# T32_ref.net
KiCad netlist of a schematic drawn in EAGLE
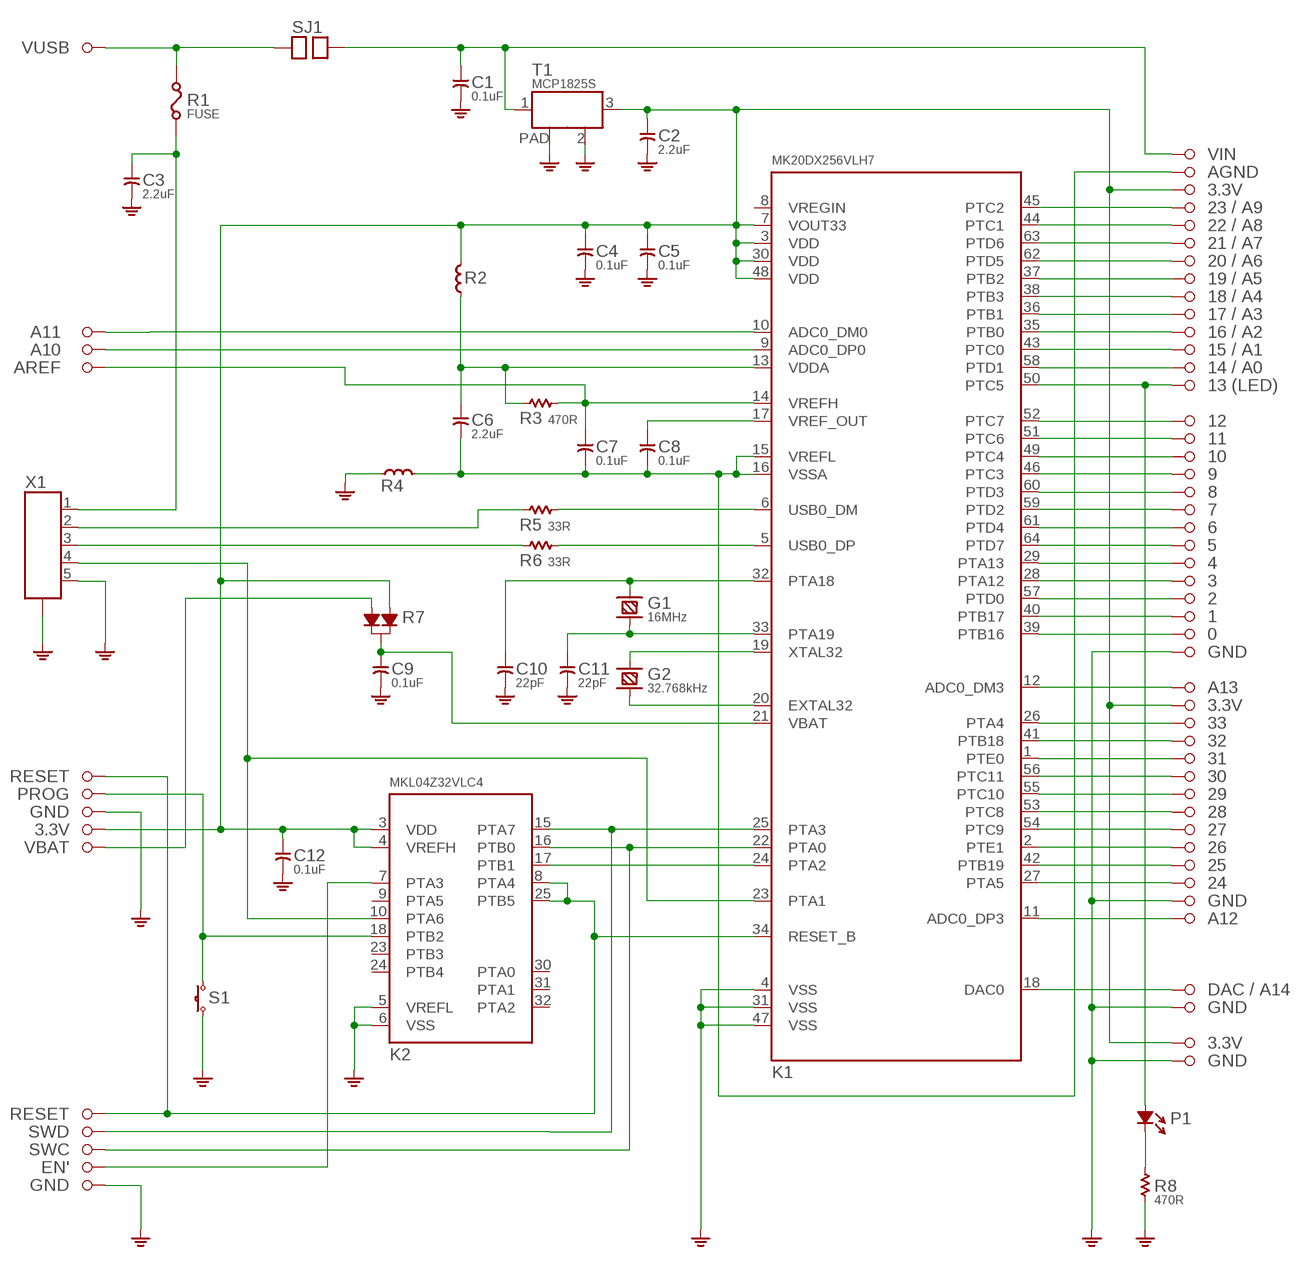
[diagram p0: schematic, sheet 1]

(export (version "E")
  (design (tool "Eeschema 10.0.6"))
  (components
    (comp (ref "C1")
      (value "0.1uF")
      (footprint "eagle-import:C0603")
      (fields (field (name "MF") "Murata Electronics") (field (name "MPN") "GRM155R71A104KA01D"))
      (libsource (lib "eagle-import") (part "CAPACITOR-0.1UF"))
    )
    (comp (ref "C2")
      (value "2.2uF")
      (footprint "eagle-import:C0805")
      (fields (field (name "MF") "Taiyo Yuden") (field (name "MPN") "TMK212B7225KG-TR"))
      (libsource (lib "eagle-import") (part "CAPACITOR-2.2UF"))
    )
    (comp (ref "C3")
      (value "2.2uF")
      (footprint "eagle-import:C0805")
      (fields (field (name "MF") "Taiyo Yuden") (field (name "MPN") "TMK212B7225KG-TR"))
      (libsource (lib "eagle-import") (part "CAPACITOR-2.2UF"))
    )
    (comp (ref "C4")
      (value "0.1uF")
      (footprint "eagle-import:C0603")
      (fields (field (name "MF") "Murata Electronics") (field (name "MPN") "GRM155R71A104KA01D"))
      (libsource (lib "eagle-import") (part "CAPACITOR-0.1UF"))
    )
    (comp (ref "C5")
      (value "0.1uF")
      (footprint "eagle-import:C0603")
      (fields (field (name "MF") "Murata Electronics") (field (name "MPN") "GRM155R71A104KA01D"))
      (libsource (lib "eagle-import") (part "CAPACITOR-0.1UF"))
    )
    (comp (ref "C6")
      (value "2.2uF")
      (footprint "eagle-import:C0805")
      (fields (field (name "MF") "Taiyo Yuden") (field (name "MPN") "TMK212B7225KG-TR"))
      (libsource (lib "eagle-import") (part "CAPACITOR-2.2UF"))
    )
    (comp (ref "C7")
      (value "0.1uF")
      (footprint "eagle-import:C0603")
      (fields (field (name "MF") "Murata Electronics") (field (name "MPN") "GRM155R71A104KA01D"))
      (libsource (lib "eagle-import") (part "CAPACITOR-0.1UF"))
    )
    (comp (ref "C8")
      (value "0.1uF")
      (footprint "eagle-import:C0603")
      (fields (field (name "MF") "Murata Electronics") (field (name "MPN") "GRM155R71A104KA01D"))
      (libsource (lib "eagle-import") (part "CAPACITOR-0.1UF"))
    )
    (comp (ref "C9")
      (value "0.1uF")
      (footprint "eagle-import:C0603")
      (fields (field (name "MF") "Murata Electronics") (field (name "MPN") "GRM155R71A104KA01D"))
      (libsource (lib "eagle-import") (part "CAPACITOR-0.1UF"))
    )
    (comp (ref "C10")
      (value "22pF")
      (footprint "eagle-import:C0603")
      (fields (field (name "MF") "Vishay / Vitramon") (field (name "MPN") "VJ0603A220JXACW1BC"))
      (libsource (lib "eagle-import") (part "CAPACITOR-22PF"))
    )
    (comp (ref "C11")
      (value "22pF")
      (footprint "eagle-import:C0603")
      (fields (field (name "MF") "Vishay / Vitramon") (field (name "MPN") "VJ0603A220JXACW1BC"))
      (libsource (lib "eagle-import") (part "CAPACITOR-22PF"))
    )
    (comp (ref "C12")
      (value "0.1uF")
      (footprint "eagle-import:C0603")
      (fields (field (name "MF") "Murata Electronics") (field (name "MPN") "GRM155R71A104KA01D"))
      (libsource (lib "eagle-import") (part "CAPACITOR-0.1UF"))
    )
    (comp (ref "G1")
      (value "16MHz")
      (footprint "eagle-import:HC49US")
      (fields (field (name "MF") "ABRACON") (field (name "MPN") "ABL-16.000MHz-B1U"))
      (libsource (lib "eagle-import") (part "CRYSTAL-HC49US"))
    )
    (comp (ref "G2")
      (value "32.768kHz")
      (footprint "eagle-import:TC26H")
      (fields (field (name "MF") "Citizen FineDevice") (field (name "MPN") " CFS206-32.768KDZF-UB"))
      (libsource (lib "eagle-import") (part "CRYSTAL-TC26H"))
    )
    (comp (ref "K1")
      (value "MK20DX256VLH7")
      (footprint "eagle-import:LQFP64-05")
      (fields (field (name "MF") "NXP"))
      (libsource (lib "eagle-import") (part "MK20DX256VLH7"))
    )
    (comp (ref "K2")
      (value "MKL04Z32VLC4")
      (footprint "eagle-import:LQFP32-08")
      (fields (field (name "MF") "PJRC") (field (name "MPN") "IC_MKL04Z32_TQFP32"))
      (libsource (lib "eagle-import") (part "MKL04Z32VLC4"))
    )
    (comp (ref "P1")
      (value "LED")
      (footprint "eagle-import:LED-0805")
      (fields (field (name "MF") "ROHM Semiconductor") (field (name "MPN") "SML-211DTT86"))
      (libsource (lib "eagle-import") (part "LED"))
    )
    (comp (ref "R1")
      (value "FUSE")
      (footprint "eagle-import:F0805")
      (fields (field (name "MF") "Bel Fuse") (field (name "MPN") "0ZCK0050FF2E"))
      (libsource (lib "eagle-import") (part "FUSE"))
    )
    (comp (ref "R2")
      (value "FERRITE")
      (footprint "eagle-import:L0603")
      (fields (field (name "MF") "Murata Electronics") (field (name "MPN") " BLM18AG601SN1D"))
      (libsource (lib "eagle-import") (part "FERRITE"))
    )
    (comp (ref "R3")
      (value "470R")
      (footprint "eagle-import:R0603")
      (fields (field (name "MF") "Vishay") (field (name "MPN") "CRCW0603470RFKEA"))
      (libsource (lib "eagle-import") (part "RESISTOR-470R"))
    )
    (comp (ref "R4")
      (value "FERRITE")
      (footprint "eagle-import:L0603")
      (fields (field (name "MF") "Murata Electronics") (field (name "MPN") " BLM18AG601SN1D"))
      (libsource (lib "eagle-import") (part "FERRITE"))
    )
    (comp (ref "R5")
      (value "33R")
      (footprint "eagle-import:R0603")
      (fields (field (name "MF") "Panasonic") (field (name "MPN") "ERJ-PA3F33R0V"))
      (libsource (lib "eagle-import") (part "RESISTOR-33R"))
    )
    (comp (ref "R6")
      (value "33R")
      (footprint "eagle-import:R0603")
      (fields (field (name "MF") "Panasonic") (field (name "MPN") "ERJ-PA3F33R0V"))
      (libsource (lib "eagle-import") (part "RESISTOR-33R"))
    )
    (comp (ref "R7")
      (value "DIODE_DUAL")
      (footprint "eagle-import:SOT-23")
      (fields (field (name "MF") "NXP Semiconductors") (field (name "MPN") "BAT54C,215"))
      (libsource (lib "eagle-import") (part "DIODE_DUAL"))
    )
    (comp (ref "R8")
      (value "470R")
      (footprint "eagle-import:R0603")
      (fields (field (name "MF") "Vishay") (field (name "MPN") "CRCW0603470RFKEA"))
      (libsource (lib "eagle-import") (part "RESISTOR-470R"))
    )
    (comp (ref "S1")
      (value "TACT_SWITCH")
      (footprint "eagle-import:ALPS_SKHH")
      (fields (field (name "MF") "ALPS") (field (name "MPN") "SKHHPKA010"))
      (libsource (lib "eagle-import") (part "TACT_SWITCH"))
    )
    (comp (ref "SJ1")
      (value "SOLDERJUMPER")
      (footprint "eagle-import:SOLDERJUMPER")
      (libsource (lib "eagle-import") (part "SOLDERJUMPER"))
    )
    (comp (ref "SX1")
      (value "PIN")
      (footprint "eagle-import:PTH_39MIL")
      (libsource (lib "eagle-import") (part "PIN"))
    )
    (comp (ref "SX2")
      (value "PIN")
      (footprint "eagle-import:PTH_39MIL")
      (libsource (lib "eagle-import") (part "PIN"))
    )
    (comp (ref "SX3")
      (value "PIN")
      (footprint "eagle-import:PTH_39MIL")
      (libsource (lib "eagle-import") (part "PIN"))
    )
    (comp (ref "SX4")
      (value "PIN")
      (footprint "eagle-import:PTH_39MIL")
      (libsource (lib "eagle-import") (part "PIN"))
    )
    (comp (ref "SX5")
      (value "PIN")
      (footprint "eagle-import:PTH_39MIL")
      (libsource (lib "eagle-import") (part "PIN"))
    )
    (comp (ref "SX6")
      (value "PIN")
      (footprint "eagle-import:PTH_39MIL")
      (libsource (lib "eagle-import") (part "PIN"))
    )
    (comp (ref "SX7")
      (value "PIN")
      (footprint "eagle-import:PTH_39MIL")
      (libsource (lib "eagle-import") (part "PIN"))
    )
    (comp (ref "SX8")
      (value "PIN")
      (footprint "eagle-import:PTH_39MIL")
      (libsource (lib "eagle-import") (part "PIN"))
    )
    (comp (ref "SX9")
      (value "PIN")
      (footprint "eagle-import:PTH_39MIL")
      (libsource (lib "eagle-import") (part "PIN"))
    )
    (comp (ref "SX10")
      (value "PIN")
      (footprint "eagle-import:PTH_39MIL")
      (libsource (lib "eagle-import") (part "PIN"))
    )
    (comp (ref "SX11")
      (value "PIN")
      (footprint "eagle-import:PTH_39MIL")
      (libsource (lib "eagle-import") (part "PIN"))
    )
    (comp (ref "SX12")
      (value "PIN")
      (footprint "eagle-import:PTH_39MIL")
      (libsource (lib "eagle-import") (part "PIN"))
    )
    (comp (ref "SX13")
      (value "PIN")
      (footprint "eagle-import:PTH_39MIL")
      (libsource (lib "eagle-import") (part "PIN"))
    )
    (comp (ref "SX14")
      (value "PIN")
      (footprint "eagle-import:PTH_39MIL")
      (libsource (lib "eagle-import") (part "PIN"))
    )
    (comp (ref "SX15")
      (value "PIN")
      (footprint "eagle-import:PTH_39MIL")
      (libsource (lib "eagle-import") (part "PIN"))
    )
    (comp (ref "SX16")
      (value "PIN")
      (footprint "eagle-import:PTH_39MIL")
      (libsource (lib "eagle-import") (part "PIN"))
    )
    (comp (ref "SX17")
      (value "PIN")
      (footprint "eagle-import:PTH_39MIL")
      (libsource (lib "eagle-import") (part "PIN"))
    )
    (comp (ref "SX18")
      (value "PIN")
      (footprint "eagle-import:PTH_39MIL")
      (libsource (lib "eagle-import") (part "PIN"))
    )
    (comp (ref "SX19")
      (value "PIN")
      (footprint "eagle-import:PTH_39MIL")
      (libsource (lib "eagle-import") (part "PIN"))
    )
    (comp (ref "SX20")
      (value "PIN")
      (footprint "eagle-import:PTH_39MIL")
      (libsource (lib "eagle-import") (part "PIN"))
    )
    (comp (ref "SX21")
      (value "PIN")
      (footprint "eagle-import:PTH_39MIL")
      (libsource (lib "eagle-import") (part "PIN"))
    )
    (comp (ref "SX22")
      (value "PIN")
      (footprint "eagle-import:PTH_39MIL")
      (libsource (lib "eagle-import") (part "PIN"))
    )
    (comp (ref "SX23")
      (value "PIN")
      (footprint "eagle-import:PTH_39MIL")
      (libsource (lib "eagle-import") (part "PIN"))
    )
    (comp (ref "SX24")
      (value "PIN")
      (footprint "eagle-import:PTH_39MIL")
      (libsource (lib "eagle-import") (part "PIN"))
    )
    (comp (ref "SX25")
      (value "PIN")
      (footprint "eagle-import:PTH_39MIL")
      (libsource (lib "eagle-import") (part "PIN"))
    )
    (comp (ref "SX26")
      (value "PIN")
      (footprint "eagle-import:PTH_39MIL")
      (libsource (lib "eagle-import") (part "PIN"))
    )
    (comp (ref "SX27")
      (value "PIN")
      (footprint "eagle-import:PTH_39MIL")
      (libsource (lib "eagle-import") (part "PIN"))
    )
    (comp (ref "SX28")
      (value "PIN")
      (footprint "eagle-import:PTH_39MIL")
      (libsource (lib "eagle-import") (part "PIN"))
    )
    (comp (ref "SX29")
      (value "PIN")
      (footprint "eagle-import:PTH_39MIL")
      (libsource (lib "eagle-import") (part "PIN"))
    )
    (comp (ref "SX30")
      (value "PIN")
      (footprint "eagle-import:PTH_39MIL")
      (libsource (lib "eagle-import") (part "PIN"))
    )
    (comp (ref "SX31")
      (value "PIN")
      (footprint "eagle-import:PTH_39MIL")
      (libsource (lib "eagle-import") (part "PIN"))
    )
    (comp (ref "SX32")
      (value "PIN")
      (footprint "eagle-import:PTH_39MIL")
      (libsource (lib "eagle-import") (part "PIN"))
    )
    (comp (ref "SX33")
      (value "PIN")
      (footprint "eagle-import:PTH_39MIL")
      (libsource (lib "eagle-import") (part "PIN"))
    )
    (comp (ref "SX34")
      (value "PIN")
      (footprint "eagle-import:PTH_39MIL")
      (libsource (lib "eagle-import") (part "PIN"))
    )
    (comp (ref "SX35")
      (value "PIN")
      (footprint "eagle-import:PTH_39MIL")
      (libsource (lib "eagle-import") (part "PIN"))
    )
    (comp (ref "SX36")
      (value "PIN")
      (footprint "eagle-import:PTH_39MIL")
      (libsource (lib "eagle-import") (part "PIN"))
    )
    (comp (ref "SX37")
      (value "PIN")
      (footprint "eagle-import:PTH_39MIL")
      (libsource (lib "eagle-import") (part "PIN"))
    )
    (comp (ref "SX38")
      (value "PIN")
      (footprint "eagle-import:PTH_39MIL")
      (libsource (lib "eagle-import") (part "PIN"))
    )
    (comp (ref "SX39")
      (value "PIN")
      (footprint "eagle-import:PTH_39MIL")
      (libsource (lib "eagle-import") (part "PIN"))
    )
    (comp (ref "SX40")
      (value "PIN")
      (footprint "eagle-import:PTH_39MIL")
      (libsource (lib "eagle-import") (part "PIN"))
    )
    (comp (ref "SX41")
      (value "PIN")
      (footprint "eagle-import:PTH_39MIL")
      (libsource (lib "eagle-import") (part "PIN"))
    )
    (comp (ref "SX42")
      (value "PIN")
      (footprint "eagle-import:PTH_39MIL")
      (libsource (lib "eagle-import") (part "PIN"))
    )
    (comp (ref "SX43")
      (value "PIN")
      (footprint "eagle-import:PTH_39MIL")
      (libsource (lib "eagle-import") (part "PIN"))
    )
    (comp (ref "SX44")
      (value "PIN")
      (footprint "eagle-import:PTH_39MIL")
      (libsource (lib "eagle-import") (part "PIN"))
    )
    (comp (ref "SX45")
      (value "PIN")
      (footprint "eagle-import:PTH_39MIL")
      (libsource (lib "eagle-import") (part "PIN"))
    )
    (comp (ref "SX46")
      (value "PIN")
      (footprint "eagle-import:PTH_39MIL")
      (libsource (lib "eagle-import") (part "PIN"))
    )
    (comp (ref "SX47")
      (value "PIN")
      (footprint "eagle-import:PTH_39MIL")
      (libsource (lib "eagle-import") (part "PIN"))
    )
    (comp (ref "SX48")
      (value "PIN")
      (footprint "eagle-import:PTH_39MIL")
      (libsource (lib "eagle-import") (part "PIN"))
    )
    (comp (ref "SX49")
      (value "PIN")
      (footprint "eagle-import:PTH_39MIL")
      (libsource (lib "eagle-import") (part "PIN"))
    )
    (comp (ref "SX50")
      (value "PIN")
      (footprint "eagle-import:PTH_39MIL")
      (libsource (lib "eagle-import") (part "PIN"))
    )
    (comp (ref "SX51")
      (value "PIN")
      (footprint "eagle-import:PTH_39MIL")
      (libsource (lib "eagle-import") (part "PIN"))
    )
    (comp (ref "SX52")
      (value "PIN")
      (footprint "eagle-import:PTH_39MIL")
      (libsource (lib "eagle-import") (part "PIN"))
    )
    (comp (ref "SX53")
      (value "PIN")
      (footprint "eagle-import:PTH_39MIL")
      (libsource (lib "eagle-import") (part "PIN"))
    )
    (comp (ref "SX54")
      (value "PIN")
      (footprint "eagle-import:PTH_39MIL")
      (libsource (lib "eagle-import") (part "PIN"))
    )
    (comp (ref "SX55")
      (value "PIN")
      (footprint "eagle-import:PTH_39MIL")
      (libsource (lib "eagle-import") (part "PIN"))
    )
    (comp (ref "SX56")
      (value "PIN")
      (footprint "eagle-import:PTH_39MIL")
      (libsource (lib "eagle-import") (part "PIN"))
    )
    (comp (ref "SX57")
      (value "PIN")
      (footprint "eagle-import:PTH_39MIL")
      (libsource (lib "eagle-import") (part "PIN"))
    )
    (comp (ref "SX58")
      (value "PIN")
      (footprint "eagle-import:PTH_39MIL")
      (libsource (lib "eagle-import") (part "PIN"))
    )
    (comp (ref "SX59")
      (value "PIN")
      (footprint "eagle-import:PTH_39MIL")
      (libsource (lib "eagle-import") (part "PIN"))
    )
    (comp (ref "SX60")
      (value "PIN")
      (footprint "eagle-import:PTH_39MIL")
      (libsource (lib "eagle-import") (part "PIN"))
    )
    (comp (ref "T1")
      (value "MCP1825S")
      (footprint "eagle-import:SOT-223")
      (fields (field (name "MF") "Microchip Technology") (field (name "MPN") "MCP1825S-3302E/DB"))
      (libsource (lib "eagle-import") (part "LDO"))
    )
    (comp (ref "X1")
      (value "MINI-USB")
      (footprint "eagle-import:MOLEX_SD-67503-010")
      (fields (field (name "MF") "MOLEX") (field (name "MPN") "0675031020"))
      (libsource (lib "eagle-import") (part "MINI-USBMOLEX_0675031230"))
    )
  )
  (nets
    (net (code "1") (name "GND") (class "Default")
      (node (ref "C1") (pin "2") (pinfunction "2_2") (pintype "passive"))
      (node (ref "C10") (pin "2") (pinfunction "2_2") (pintype "passive"))
      (node (ref "C11") (pin "2") (pinfunction "2_2") (pintype "passive"))
      (node (ref "C12") (pin "2") (pinfunction "2_2") (pintype "passive"))
      (node (ref "C2") (pin "2") (pinfunction "2_2") (pintype "passive"))
      (node (ref "C3") (pin "2") (pinfunction "2_2") (pintype "passive"))
      (node (ref "C4") (pin "2") (pinfunction "2_2") (pintype "passive"))
      (node (ref "C5") (pin "2") (pinfunction "2_2") (pintype "passive"))
      (node (ref "C9") (pin "2") (pinfunction "2_2") (pintype "passive"))
      (node (ref "K1") (pin "31") (pinfunction "VSS_31") (pintype "bidirectional"))
      (node (ref "K1") (pin "4") (pinfunction "VSS_4") (pintype "bidirectional"))
      (node (ref "K1") (pin "47") (pinfunction "VSS_47") (pintype "bidirectional"))
      (node (ref "K2") (pin "5") (pinfunction "VREFL_5") (pintype "bidirectional"))
      (node (ref "K2") (pin "6") (pinfunction "VSS_6") (pintype "bidirectional"))
      (node (ref "R4") (pin "1") (pinfunction "1_1") (pintype "passive"))
      (node (ref "R8") (pin "1") (pinfunction "1_1") (pintype "passive"))
      (node (ref "S1") (pin "3") (pinfunction "3_3") (pintype "passive"))
      (node (ref "S1") (pin "4") (pinfunction "3_4") (pintype "passive"))
      (node (ref "SX32") (pin "1") (pinfunction "P$1_1") (pintype "bidirectional"))
      (node (ref "SX42") (pin "1") (pinfunction "P$1_1") (pintype "bidirectional"))
      (node (ref "SX50") (pin "1") (pinfunction "P$1_1") (pintype "bidirectional"))
      (node (ref "SX53") (pin "1") (pinfunction "P$1_1") (pintype "bidirectional"))
      (node (ref "SX55") (pin "1") (pinfunction "P$1_1") (pintype "bidirectional"))
      (node (ref "SX60") (pin "1") (pinfunction "P$1_1") (pintype "bidirectional"))
      (node (ref "T1") (pin "2") (pinfunction "GND_2") (pintype "bidirectional"))
      (node (ref "T1") (pin "PAD") (pinfunction "PAD_PAD") (pintype "bidirectional"))
      (node (ref "X1") (pin "5") (pinfunction "5_5") (pintype "input"))
      (node (ref "X1") (pin "P$1") (pinfunction "CASE_P$1") (pintype "input"))
      (node (ref "X1") (pin "P$2") (pinfunction "CASE_P$2") (pintype "input"))
      (node (ref "X1") (pin "P$3") (pinfunction "CASE_P$3") (pintype "input"))
      (node (ref "X1") (pin "P$4") (pinfunction "CASE_P$4") (pintype "input"))
      (node (ref "X1") (pin "P$5") (pinfunction "CASE_P$5") (pintype "input"))
      (node (ref "X1") (pin "P$6") (pinfunction "CASE_P$6") (pintype "input"))
    )
    (net (code "2") (name "Net-(C3-Pad1)") (class "Default")
      (node (ref "C3") (pin "1") (pinfunction "1_1") (pintype "passive"))
      (node (ref "R1") (pin "1") (pinfunction "1_1") (pintype "bidirectional"))
      (node (ref "X1") (pin "1") (pinfunction "1_1") (pintype "input"))
    )
    (net (code "3") (name "Net-(G2-1)") (class "Default")
      (node (ref "G2") (pin "2") (pinfunction "1_2") (pintype "passive"))
      (node (ref "K1") (pin "19") (pinfunction "XTAL32_19") (pintype "bidirectional"))
    )
    (net (code "4") (name "Net-(G2-2)") (class "Default")
      (node (ref "G2") (pin "1") (pinfunction "2_1") (pintype "passive"))
      (node (ref "K1") (pin "20") (pinfunction "EXTAL32_20") (pintype "bidirectional"))
    )
    (net (code "5") (name "Net-(K1-ADC0_DM0)") (class "Default")
      (node (ref "K1") (pin "10") (pinfunction "ADC0_DM0_10") (pintype "bidirectional"))
      (node (ref "SX12") (pin "1") (pinfunction "P$1_1") (pintype "bidirectional"))
    )
    (net (code "6") (name "Net-(K1-ADC0_DM3)") (class "Default")
      (node (ref "K1") (pin "12") (pinfunction "ADC0_DM3_12") (pintype "bidirectional"))
      (node (ref "SX33") (pin "1") (pinfunction "P$1_1") (pintype "bidirectional"))
    )
    (net (code "7") (name "Net-(K1-ADC0_DP0)") (class "Default")
      (node (ref "K1") (pin "9") (pinfunction "ADC0_DP0_9") (pintype "bidirectional"))
      (node (ref "SX14") (pin "1") (pinfunction "P$1_1") (pintype "bidirectional"))
    )
    (net (code "8") (name "Net-(K1-ADC0_DP3)") (class "Default")
      (node (ref "K1") (pin "11") (pinfunction "ADC0_DP3_11") (pintype "bidirectional"))
      (node (ref "SX51") (pin "1") (pinfunction "P$1_1") (pintype "bidirectional"))
    )
    (net (code "9") (name "Net-(K1-DAC0)") (class "Default")
      (node (ref "K1") (pin "18") (pinfunction "DAC0_18") (pintype "bidirectional"))
      (node (ref "SX52") (pin "1") (pinfunction "P$1_1") (pintype "bidirectional"))
    )
    (net (code "10") (name "Net-(K1-PTA0)") (class "Default")
      (node (ref "K1") (pin "22") (pinfunction "PTA0_22") (pintype "bidirectional"))
      (node (ref "K2") (pin "16") (pinfunction "PTB0_16") (pintype "bidirectional"))
      (node (ref "SX58") (pin "1") (pinfunction "P$1_1") (pintype "bidirectional"))
    )
    (net (code "11") (name "Net-(K1-PTA1)") (class "Default")
      (node (ref "K1") (pin "23") (pinfunction "PTA1_23") (pintype "bidirectional"))
      (node (ref "K2") (pin "10") (pinfunction "PTA6_10") (pintype "bidirectional"))
      (node (ref "X1") (pin "4") (pinfunction "4_4") (pintype "input"))
    )
    (net (code "12") (name "Net-(K1-PTA2)") (class "Default")
      (node (ref "K1") (pin "24") (pinfunction "PTA2_24") (pintype "bidirectional"))
      (node (ref "K2") (pin "17") (pinfunction "PTB1_17") (pintype "bidirectional"))
    )
    (net (code "13") (name "Net-(K1-PTA3)") (class "Default")
      (node (ref "K1") (pin "25") (pinfunction "PTA3_25") (pintype "bidirectional"))
      (node (ref "K2") (pin "15") (pinfunction "PTA7_15") (pintype "bidirectional"))
      (node (ref "SX57") (pin "1") (pinfunction "P$1_1") (pintype "bidirectional"))
    )
    (net (code "14") (name "Net-(K1-PTA4)") (class "Default")
      (node (ref "K1") (pin "26") (pinfunction "PTA4_26") (pintype "bidirectional"))
      (node (ref "SX35") (pin "1") (pinfunction "P$1_1") (pintype "bidirectional"))
    )
    (net (code "15") (name "Net-(K1-PTA5)") (class "Default")
      (node (ref "K1") (pin "27") (pinfunction "PTA5_27") (pintype "bidirectional"))
      (node (ref "SX49") (pin "1") (pinfunction "P$1_1") (pintype "bidirectional"))
    )
    (net (code "16") (name "Net-(K1-PTA12)") (class "Default")
      (node (ref "K1") (pin "28") (pinfunction "PTA12_28") (pintype "bidirectional"))
      (node (ref "SX28") (pin "1") (pinfunction "P$1_1") (pintype "bidirectional"))
    )
    (net (code "17") (name "Net-(K1-PTA13)") (class "Default")
      (node (ref "K1") (pin "29") (pinfunction "PTA13_29") (pintype "bidirectional"))
      (node (ref "SX27") (pin "1") (pinfunction "P$1_1") (pintype "bidirectional"))
    )
    (net (code "18") (name "Net-(K1-PTA18)") (class "Default")
      (node (ref "C10") (pin "1") (pinfunction "1_1") (pintype "passive"))
      (node (ref "G1") (pin "1") (pinfunction "1_1") (pintype "passive"))
      (node (ref "K1") (pin "32") (pinfunction "PTA18_32") (pintype "bidirectional"))
    )
    (net (code "19") (name "Net-(K1-PTA19)") (class "Default")
      (node (ref "C11") (pin "1") (pinfunction "1_1") (pintype "passive"))
      (node (ref "G1") (pin "2") (pinfunction "2_2") (pintype "passive"))
      (node (ref "K1") (pin "33") (pinfunction "PTA19_33") (pintype "bidirectional"))
    )
    (net (code "20") (name "Net-(K1-PTB0)") (class "Default")
      (node (ref "K1") (pin "35") (pinfunction "PTB0_35") (pintype "bidirectional"))
      (node (ref "SX13") (pin "1") (pinfunction "P$1_1") (pintype "bidirectional"))
    )
    (net (code "21") (name "Net-(K1-PTB1)") (class "Default")
      (node (ref "K1") (pin "36") (pinfunction "PTB1_36") (pintype "bidirectional"))
      (node (ref "SX11") (pin "1") (pinfunction "P$1_1") (pintype "bidirectional"))
    )
    (net (code "22") (name "Net-(K1-PTB2)") (class "Default")
      (node (ref "K1") (pin "37") (pinfunction "PTB2_37") (pintype "bidirectional"))
      (node (ref "SX9") (pin "1") (pinfunction "P$1_1") (pintype "bidirectional"))
    )
    (net (code "23") (name "Net-(K1-PTB3)") (class "Default")
      (node (ref "K1") (pin "38") (pinfunction "PTB3_38") (pintype "bidirectional"))
      (node (ref "SX10") (pin "1") (pinfunction "P$1_1") (pintype "bidirectional"))
    )
    (net (code "24") (name "Net-(K1-PTB16)") (class "Default")
      (node (ref "K1") (pin "39") (pinfunction "PTB16_39") (pintype "bidirectional"))
      (node (ref "SX31") (pin "1") (pinfunction "P$1_1") (pintype "bidirectional"))
    )
    (net (code "25") (name "Net-(K1-PTB17)") (class "Default")
      (node (ref "K1") (pin "40") (pinfunction "PTB17_40") (pintype "bidirectional"))
      (node (ref "SX30") (pin "1") (pinfunction "P$1_1") (pintype "bidirectional"))
    )
    (net (code "26") (name "Net-(K1-PTB18)") (class "Default")
      (node (ref "K1") (pin "41") (pinfunction "PTB18_41") (pintype "bidirectional"))
      (node (ref "SX36") (pin "1") (pinfunction "P$1_1") (pintype "bidirectional"))
    )
    (net (code "27") (name "Net-(K1-PTB19)") (class "Default")
      (node (ref "K1") (pin "42") (pinfunction "PTB19_42") (pintype "bidirectional"))
      (node (ref "SX48") (pin "1") (pinfunction "P$1_1") (pintype "bidirectional"))
    )
    (net (code "28") (name "Net-(K1-PTC0)") (class "Default")
      (node (ref "K1") (pin "43") (pinfunction "PTC0_43") (pintype "bidirectional"))
      (node (ref "SX15") (pin "1") (pinfunction "P$1_1") (pintype "bidirectional"))
    )
    (net (code "29") (name "Net-(K1-PTC1)") (class "Default")
      (node (ref "K1") (pin "44") (pinfunction "PTC1_44") (pintype "bidirectional"))
      (node (ref "SX6") (pin "1") (pinfunction "P$1_1") (pintype "bidirectional"))
    )
    (net (code "30") (name "Net-(K1-PTC2)") (class "Default")
      (node (ref "K1") (pin "45") (pinfunction "PTC2_45") (pintype "bidirectional"))
      (node (ref "SX5") (pin "1") (pinfunction "P$1_1") (pintype "bidirectional"))
    )
    (net (code "31") (name "Net-(K1-PTC3)") (class "Default")
      (node (ref "K1") (pin "46") (pinfunction "PTC3_46") (pintype "bidirectional"))
      (node (ref "SX22") (pin "1") (pinfunction "P$1_1") (pintype "bidirectional"))
    )
    (net (code "32") (name "Net-(K1-PTC4)") (class "Default")
      (node (ref "K1") (pin "49") (pinfunction "PTC4_49") (pintype "bidirectional"))
      (node (ref "SX21") (pin "1") (pinfunction "P$1_1") (pintype "bidirectional"))
    )
    (net (code "33") (name "Net-(K1-PTC5)") (class "Default")
      (node (ref "K1") (pin "50") (pinfunction "PTC5_50") (pintype "bidirectional"))
      (node (ref "P1") (pin "+") (pinfunction "+_+") (pintype "passive"))
      (node (ref "SX18") (pin "1") (pinfunction "P$1_1") (pintype "bidirectional"))
    )
    (net (code "34") (name "Net-(K1-PTC6)") (class "Default")
      (node (ref "K1") (pin "51") (pinfunction "PTC6_51") (pintype "bidirectional"))
      (node (ref "SX20") (pin "1") (pinfunction "P$1_1") (pintype "bidirectional"))
    )
    (net (code "35") (name "Net-(K1-PTC7)") (class "Default")
      (node (ref "K1") (pin "52") (pinfunction "PTC7_52") (pintype "bidirectional"))
      (node (ref "SX19") (pin "1") (pinfunction "P$1_1") (pintype "bidirectional"))
    )
    (net (code "36") (name "Net-(K1-PTC8)") (class "Default")
      (node (ref "K1") (pin "53") (pinfunction "PTC8_53") (pintype "bidirectional"))
      (node (ref "SX43") (pin "1") (pinfunction "P$1_1") (pintype "bidirectional"))
    )
    (net (code "37") (name "Net-(K1-PTC9)") (class "Default")
      (node (ref "K1") (pin "54") (pinfunction "PTC9_54") (pintype "bidirectional"))
      (node (ref "SX45") (pin "1") (pinfunction "P$1_1") (pintype "bidirectional"))
    )
    (net (code "38") (name "Net-(K1-PTC10)") (class "Default")
      (node (ref "K1") (pin "55") (pinfunction "PTC10_55") (pintype "bidirectional"))
      (node (ref "SX41") (pin "1") (pinfunction "P$1_1") (pintype "bidirectional"))
    )
    (net (code "39") (name "Net-(K1-PTC11)") (class "Default")
      (node (ref "K1") (pin "56") (pinfunction "PTC11_56") (pintype "bidirectional"))
      (node (ref "SX39") (pin "1") (pinfunction "P$1_1") (pintype "bidirectional"))
    )
    (net (code "40") (name "Net-(K1-PTD0)") (class "Default")
      (node (ref "K1") (pin "57") (pinfunction "PTD0_57") (pintype "bidirectional"))
      (node (ref "SX29") (pin "1") (pinfunction "P$1_1") (pintype "bidirectional"))
    )
    (net (code "41") (name "Net-(K1-PTD1)") (class "Default")
      (node (ref "K1") (pin "58") (pinfunction "PTD1_58") (pintype "bidirectional"))
      (node (ref "SX17") (pin "1") (pinfunction "P$1_1") (pintype "bidirectional"))
    )
    (net (code "42") (name "Net-(K1-PTD2)") (class "Default")
      (node (ref "K1") (pin "59") (pinfunction "PTD2_59") (pintype "bidirectional"))
      (node (ref "SX24") (pin "1") (pinfunction "P$1_1") (pintype "bidirectional"))
    )
    (net (code "43") (name "Net-(K1-PTD3)") (class "Default")
      (node (ref "K1") (pin "60") (pinfunction "PTD3_60") (pintype "bidirectional"))
      (node (ref "SX23") (pin "1") (pinfunction "P$1_1") (pintype "bidirectional"))
    )
    (net (code "44") (name "Net-(K1-PTD4)") (class "Default")
      (node (ref "K1") (pin "61") (pinfunction "PTD4_61") (pintype "bidirectional"))
      (node (ref "SX25") (pin "1") (pinfunction "P$1_1") (pintype "bidirectional"))
    )
    (net (code "45") (name "Net-(K1-PTD5)") (class "Default")
      (node (ref "K1") (pin "62") (pinfunction "PTD5_62") (pintype "bidirectional"))
      (node (ref "SX8") (pin "1") (pinfunction "P$1_1") (pintype "bidirectional"))
    )
    (net (code "46") (name "Net-(K1-PTD6)") (class "Default")
      (node (ref "K1") (pin "63") (pinfunction "PTD6_63") (pintype "bidirectional"))
      (node (ref "SX7") (pin "1") (pinfunction "P$1_1") (pintype "bidirectional"))
    )
    (net (code "47") (name "Net-(K1-PTD7)") (class "Default")
      (node (ref "K1") (pin "64") (pinfunction "PTD7_64") (pintype "bidirectional"))
      (node (ref "SX26") (pin "1") (pinfunction "P$1_1") (pintype "bidirectional"))
    )
    (net (code "48") (name "Net-(K1-PTE0)") (class "Default")
      (node (ref "K1") (pin "1") (pinfunction "PTE0_1") (pintype "bidirectional"))
      (node (ref "SX37") (pin "1") (pinfunction "P$1_1") (pintype "bidirectional"))
    )
    (net (code "49") (name "Net-(K1-PTE1)") (class "Default")
      (node (ref "K1") (pin "2") (pinfunction "PTE1_2") (pintype "bidirectional"))
      (node (ref "SX47") (pin "1") (pinfunction "P$1_1") (pintype "bidirectional"))
    )
    (net (code "50") (name "Net-(K1-RESET_B)") (class "Default")
      (node (ref "K1") (pin "34") (pinfunction "RESET_B_34") (pintype "bidirectional"))
      (node (ref "K2") (pin "25") (pinfunction "PTB5_25") (pintype "bidirectional"))
      (node (ref "K2") (pin "8") (pinfunction "PTA4_8") (pintype "bidirectional"))
      (node (ref "SX38") (pin "1") (pinfunction "P$1_1") (pintype "bidirectional"))
      (node (ref "SX56") (pin "1") (pinfunction "P$1_1") (pintype "bidirectional"))
    )
    (net (code "51") (name "Net-(K1-USB0_DM)") (class "Default")
      (node (ref "K1") (pin "6") (pinfunction "USB0_DM_6") (pintype "bidirectional"))
      (node (ref "R5") (pin "2") (pinfunction "2_2") (pintype "passive"))
    )
    (net (code "52") (name "Net-(K1-USB0_DP)") (class "Default")
      (node (ref "K1") (pin "5") (pinfunction "USB0_DP_5") (pintype "bidirectional"))
      (node (ref "R6") (pin "2") (pinfunction "2_2") (pintype "passive"))
    )
    (net (code "53") (name "Net-(K1-VBAT)") (class "Default")
      (node (ref "C9") (pin "1") (pinfunction "1_1") (pintype "passive"))
      (node (ref "K1") (pin "21") (pinfunction "VBAT_21") (pintype "bidirectional"))
      (node (ref "R7") (pin "3") (pinfunction "3_3") (pintype "bidirectional"))
    )
    (net (code "54") (name "Net-(K1-VDDA)") (class "Default")
      (node (ref "C6") (pin "1") (pinfunction "1_1") (pintype "passive"))
      (node (ref "K1") (pin "13") (pinfunction "VDDA_13") (pintype "bidirectional"))
      (node (ref "R2") (pin "1") (pinfunction "1_1") (pintype "passive"))
      (node (ref "R3") (pin "1") (pinfunction "1_1") (pintype "passive"))
    )
    (net (code "55") (name "Net-(K1-VOUT33)") (class "Default")
      (node (ref "C12") (pin "1") (pinfunction "1_1") (pintype "passive"))
      (node (ref "C2") (pin "1") (pinfunction "1_1") (pintype "passive"))
      (node (ref "C4") (pin "1") (pinfunction "1_1") (pintype "passive"))
      (node (ref "C5") (pin "1") (pinfunction "1_1") (pintype "passive"))
      (node (ref "K1") (pin "3") (pinfunction "VDD_3") (pintype "bidirectional"))
      (node (ref "K1") (pin "30") (pinfunction "VDD_30") (pintype "bidirectional"))
      (node (ref "K1") (pin "48") (pinfunction "VDD_48") (pintype "bidirectional"))
      (node (ref "K1") (pin "7") (pinfunction "VOUT33_7") (pintype "bidirectional"))
      (node (ref "K2") (pin "3") (pinfunction "VDD_3") (pintype "bidirectional"))
      (node (ref "K2") (pin "4") (pinfunction "VREFH_4") (pintype "bidirectional"))
      (node (ref "R2") (pin "2") (pinfunction "2_2") (pintype "passive"))
      (node (ref "R7") (pin "1") (pinfunction "1_1") (pintype "bidirectional"))
      (node (ref "SX34") (pin "1") (pinfunction "P$1_1") (pintype "bidirectional"))
      (node (ref "SX4") (pin "1") (pinfunction "P$1_1") (pintype "bidirectional"))
      (node (ref "SX44") (pin "1") (pinfunction "P$1_1") (pintype "bidirectional"))
      (node (ref "SX54") (pin "1") (pinfunction "P$1_1") (pintype "bidirectional"))
      (node (ref "T1") (pin "3") (pinfunction "OUT_3") (pintype "bidirectional"))
    )
    (net (code "56") (name "Net-(K1-VREFH)") (class "Default")
      (node (ref "C7") (pin "1") (pinfunction "1_1") (pintype "passive"))
      (node (ref "K1") (pin "14") (pinfunction "VREFH_14") (pintype "bidirectional"))
      (node (ref "R3") (pin "2") (pinfunction "2_2") (pintype "passive"))
      (node (ref "SX16") (pin "1") (pinfunction "P$1_1") (pintype "bidirectional"))
    )
    (net (code "57") (name "Net-(K1-VREFL)") (class "Default")
      (node (ref "C6") (pin "2") (pinfunction "2_2") (pintype "passive"))
      (node (ref "C7") (pin "2") (pinfunction "2_2") (pintype "passive"))
      (node (ref "C8") (pin "2") (pinfunction "2_2") (pintype "passive"))
      (node (ref "K1") (pin "15") (pinfunction "VREFL_15") (pintype "bidirectional"))
      (node (ref "K1") (pin "16") (pinfunction "VSSA_16") (pintype "bidirectional"))
      (node (ref "R4") (pin "2") (pinfunction "2_2") (pintype "passive"))
      (node (ref "SX3") (pin "1") (pinfunction "P$1_1") (pintype "bidirectional"))
    )
    (net (code "58") (name "Net-(K1-VREF_OUT)") (class "Default")
      (node (ref "C8") (pin "1") (pinfunction "1_1") (pintype "passive"))
      (node (ref "K1") (pin "17") (pinfunction "VREF_OUT_17") (pintype "bidirectional"))
    )
    (net (code "59") (name "Net-(K2-PTA3)") (class "Default")
      (node (ref "K2") (pin "7") (pinfunction "PTA3_7") (pintype "bidirectional"))
      (node (ref "SX59") (pin "1") (pinfunction "P$1_1") (pintype "bidirectional"))
    )
    (net (code "60") (name "Net-(K2-PTB2)") (class "Default")
      (node (ref "K2") (pin "18") (pinfunction "PTB2_18") (pintype "bidirectional"))
      (node (ref "S1") (pin "1") (pinfunction "1_1") (pintype "passive"))
      (node (ref "S1") (pin "2") (pinfunction "1_2") (pintype "passive"))
      (node (ref "SX40") (pin "1") (pinfunction "P$1_1") (pintype "bidirectional"))
    )
    (net (code "61") (name "Net-(P1-Pad-)") (class "Default")
      (node (ref "P1") (pin "-") (pinfunction "-_-") (pintype "passive"))
      (node (ref "R8") (pin "2") (pinfunction "2_2") (pintype "passive"))
    )
    (net (code "62") (name "Net-(R5-Pad1)") (class "Default")
      (node (ref "R5") (pin "1") (pinfunction "1_1") (pintype "passive"))
      (node (ref "X1") (pin "2") (pinfunction "2_2") (pintype "input"))
    )
    (net (code "63") (name "Net-(R6-Pad1)") (class "Default")
      (node (ref "R6") (pin "1") (pinfunction "1_1") (pintype "passive"))
      (node (ref "X1") (pin "3") (pinfunction "3_3") (pintype "input"))
    )
    (net (code "64") (name "Net-(SX1-P$1)") (class "Default")
      (node (ref "R1") (pin "2") (pinfunction "2_2") (pintype "bidirectional"))
      (node (ref "SJ1") (pin "1") (pinfunction "1_1") (pintype "passive"))
      (node (ref "SX1") (pin "1") (pinfunction "P$1_1") (pintype "bidirectional"))
    )
    (net (code "65") (name "Net-(SX2-P$1)") (class "Default")
      (node (ref "C1") (pin "1") (pinfunction "1_1") (pintype "passive"))
      (node (ref "SJ1") (pin "2") (pinfunction "2_2") (pintype "passive"))
      (node (ref "SX2") (pin "1") (pinfunction "P$1_1") (pintype "bidirectional"))
      (node (ref "T1") (pin "1") (pinfunction "IN_1") (pintype "bidirectional"))
    )
    (net (code "66") (name "Net-(SX46-P$1)") (class "Default")
      (node (ref "R7") (pin "2") (pinfunction "2_2") (pintype "bidirectional"))
      (node (ref "SX46") (pin "1") (pinfunction "P$1_1") (pintype "bidirectional"))
    )
    (net (code "67") (name "unconnected-(K1-VREGIN-Pad8)") (class "Default")
      (node (ref "K1") (pin "8") (pinfunction "VREGIN_8") (pintype "bidirectional"))
    )
    (net (code "68") (name "unconnected-(K2-PTA0-Pad30)") (class "Default")
      (node (ref "K2") (pin "30") (pinfunction "PTA0_30") (pintype "bidirectional"))
    )
    (net (code "69") (name "unconnected-(K2-PTA1-Pad31)") (class "Default")
      (node (ref "K2") (pin "31") (pinfunction "PTA1_31") (pintype "bidirectional"))
    )
    (net (code "70") (name "unconnected-(K2-PTA2-Pad32)") (class "Default")
      (node (ref "K2") (pin "32") (pinfunction "PTA2_32") (pintype "bidirectional"))
    )
    (net (code "71") (name "unconnected-(K2-PTA5-Pad9)") (class "Default")
      (node (ref "K2") (pin "9") (pinfunction "PTA5_9") (pintype "bidirectional"))
    )
    (net (code "72") (name "unconnected-(K2-PTB3-Pad23)") (class "Default")
      (node (ref "K2") (pin "23") (pinfunction "PTB3_23") (pintype "bidirectional"))
    )
    (net (code "73") (name "unconnected-(K2-PTB4-Pad24)") (class "Default")
      (node (ref "K2") (pin "24") (pinfunction "PTB4_24") (pintype "bidirectional"))
    )
  )
)
